# dummyload1.net
KiCad netlist of a schematic drawn in EAGLE
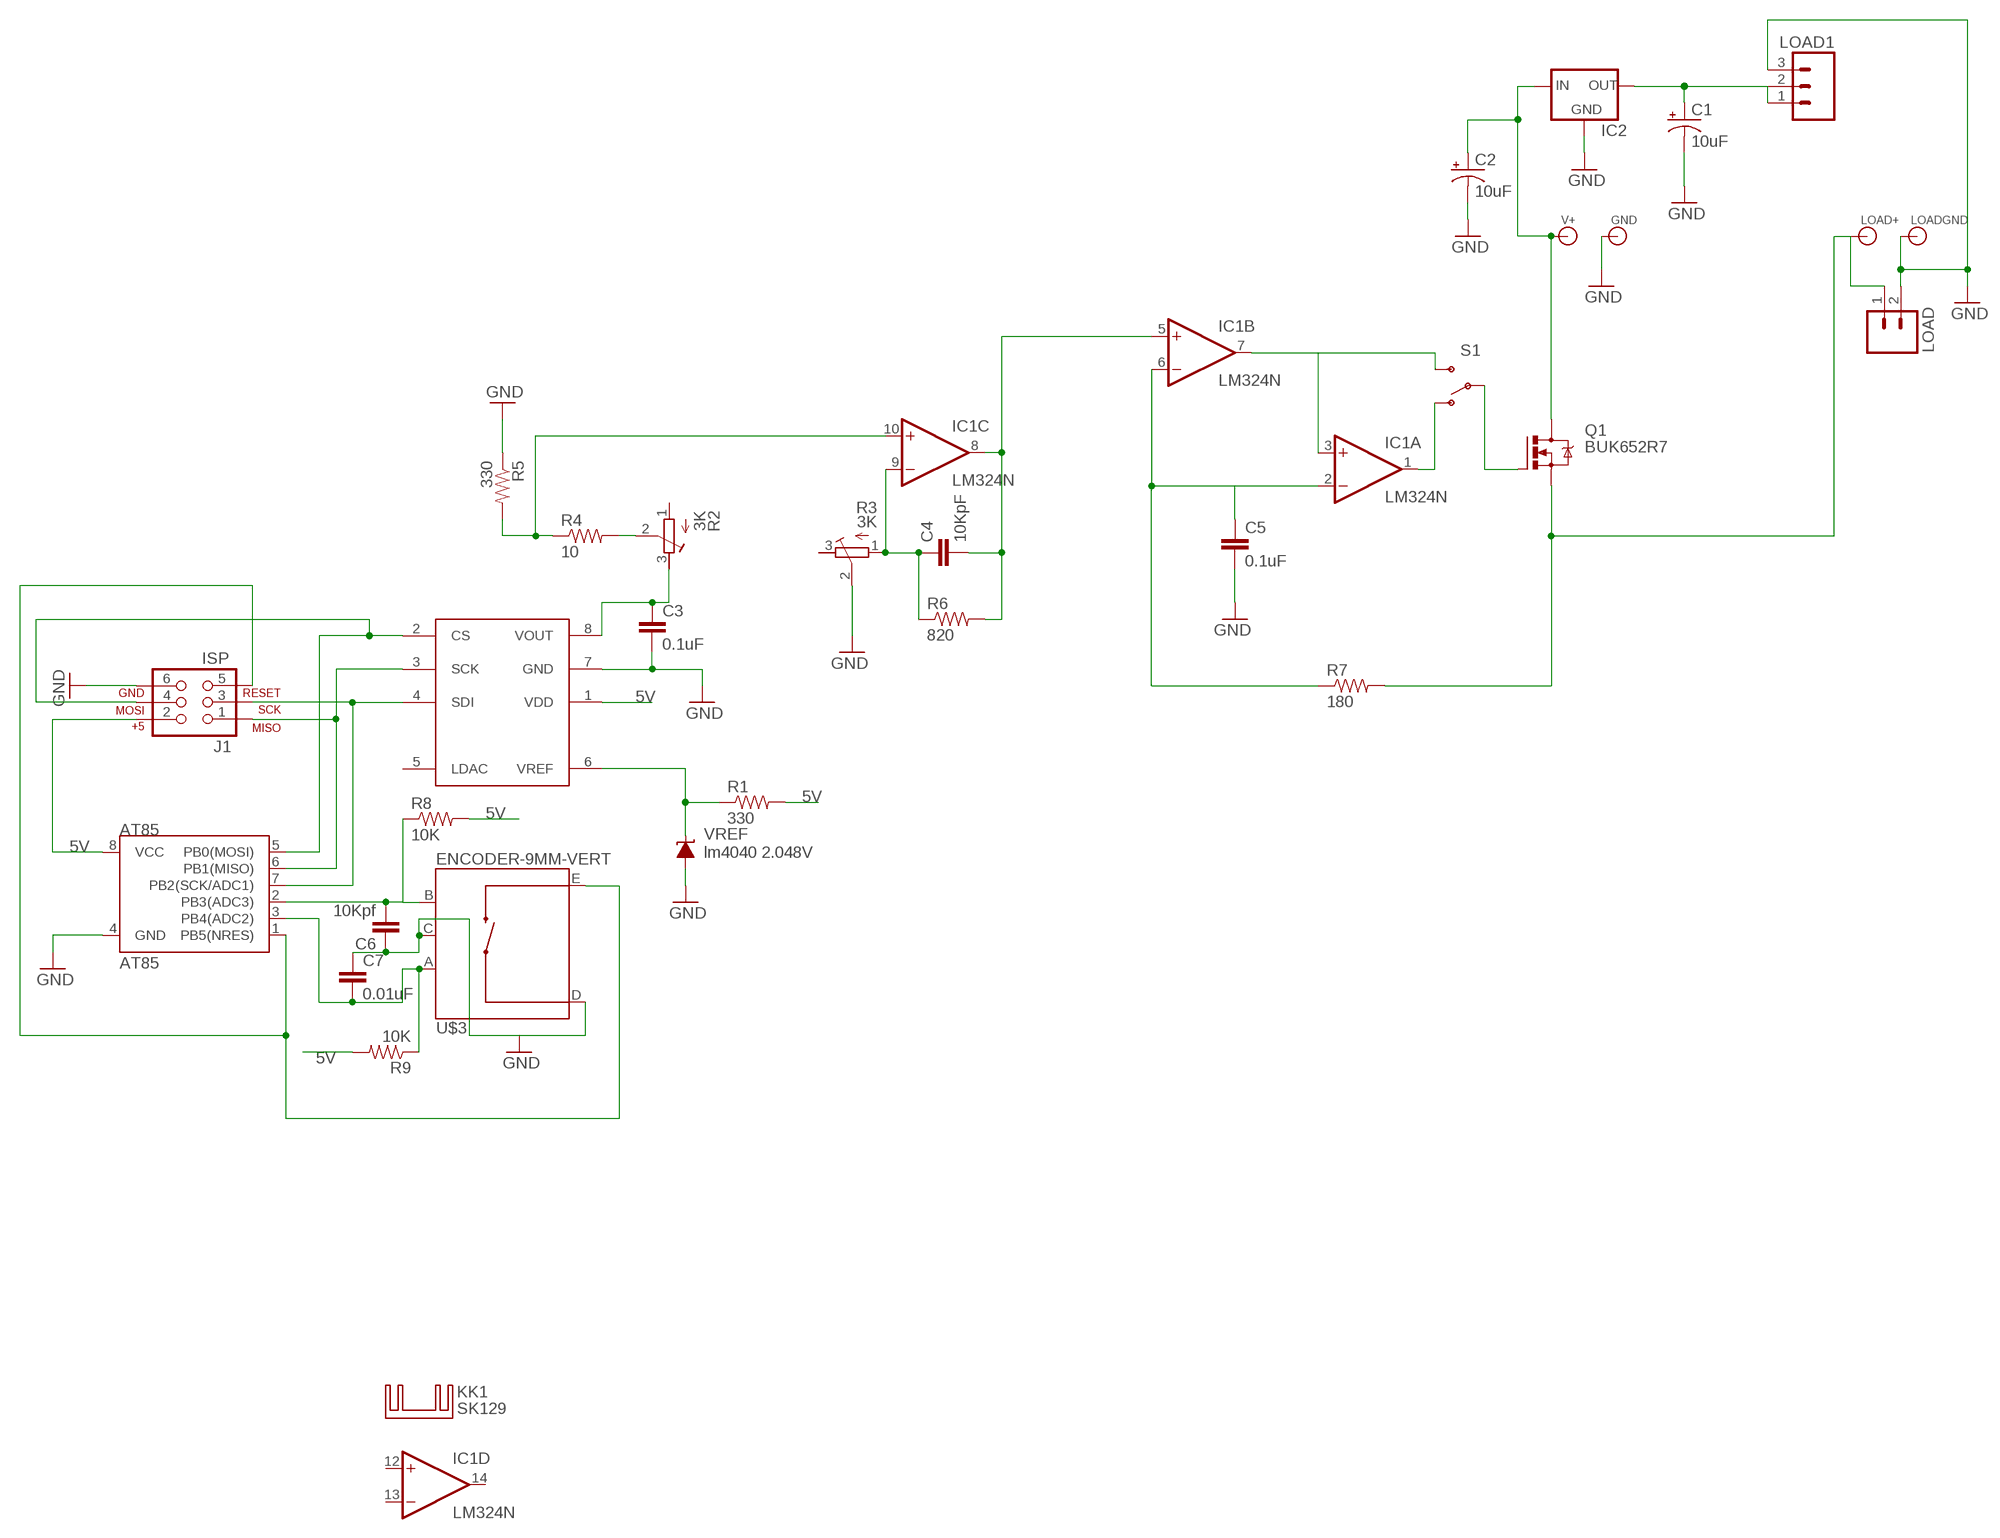
[diagram p0: schematic, sheet 1]

(export (version "E")
  (design (tool "Eeschema 10.0.6"))
  (components
    (comp (ref "AT85")
      (value "AT85")
      (footprint "eagle-import:DIP08")
      (libsource (lib "eagle-import") (part "ATTINY45DIP8"))
    )
    (comp (ref "C1")
      (value "10uF")
      (footprint "eagle-import:CPOL-RADIAL-10UF-25V")
      (libsource (lib "eagle-import") (part "CAP_POLPTH2"))
    )
    (comp (ref "C2")
      (value "10uF")
      (footprint "eagle-import:CPOL-RADIAL-10UF-25V")
      (libsource (lib "eagle-import") (part "CAP_POLPTH2"))
    )
    (comp (ref "C3")
      (value "0.1uF")
      (footprint "eagle-import:CAP-PTH-SMALL2")
      (libsource (lib "eagle-import") (part "CAPPTH2"))
    )
    (comp (ref "C4")
      (value "10KpF")
      (footprint "eagle-import:CAP-PTH-SMALL2")
      (libsource (lib "eagle-import") (part "CAPPTH2"))
    )
    (comp (ref "C5")
      (value "0.1uF")
      (footprint "eagle-import:CAP-PTH-SMALL2")
      (libsource (lib "eagle-import") (part "CAPPTH2"))
    )
    (comp (ref "C6")
      (value "10Kpf")
      (footprint "eagle-import:CAP-PTH-SMALL2")
      (libsource (lib "eagle-import") (part "CAPPTH2"))
    )
    (comp (ref "C7")
      (value "0.01uF")
      (footprint "eagle-import:CAP-PTH-SMALL2")
      (libsource (lib "eagle-import") (part "CAPPTH2"))
    )
    (comp (ref "GND")
      (value "BANANA_CONN")
      (footprint "eagle-import:BANANA_CONN")
      (libsource (lib "eagle-import") (part "BANANA_CONN"))
    )
    (comp (ref "IC1")
      (value "LM324N")
      (footprint "eagle-import:DIL14")
      (libsource (lib "eagle-import") (part "LM324N"))
    )
    (comp (ref "IC2")
      (value "V_REG_78XXSINK")
      (footprint "eagle-import:TO220-IGO")
      (libsource (lib "eagle-import") (part "V_REG_78XXSINK"))
    )
    (comp (ref "J1")
      (value "ISP")
      (footprint "eagle-import:2X3-NS")
      (libsource (lib "eagle-import") (part "AVR_SPI_PRG_6NS"))
    )
    (comp (ref "KK1")
      (value "SK129")
      (footprint "eagle-import:SK129-HOLE")
      (libsource (lib "eagle-import") (part "SK129"))
    )
    (comp (ref "LOAD")
      (value "M02LOCK")
      (footprint "eagle-import:1X02_LOCK")
      (libsource (lib "eagle-import") (part "M02LOCK"))
    )
    (comp (ref "LOAD+")
      (value "BANANA_CONN")
      (footprint "eagle-import:BANANA_CONN")
      (libsource (lib "eagle-import") (part "BANANA_CONN"))
    )
    (comp (ref "LOAD1")
      (value "M031X03_NO_SILK")
      (footprint "eagle-import:1X03_NO_SILK")
      (libsource (lib "eagle-import") (part "M031X03_NO_SILK"))
    )
    (comp (ref "LOADGND")
      (value "BANANA_CONN")
      (footprint "eagle-import:BANANA_CONN")
      (libsource (lib "eagle-import") (part "BANANA_CONN"))
    )
    (comp (ref "Q1")
      (value "BUK652R7")
      (footprint "eagle-import:TO220BV")
      (libsource (lib "eagle-import") (part "IRF540"))
    )
    (comp (ref "R1")
      (value "330")
      (footprint "eagle-import:AXIAL-0.4")
      (libsource (lib "eagle-import") (part "RESISTORPTH-1/4W"))
    )
    (comp (ref "R2")
      (value "3K")
      (footprint "eagle-import:RTRIM3296W")
      (libsource (lib "eagle-import") (part "R-TRIMM3296W"))
    )
    (comp (ref "R3")
      (value "3K")
      (footprint "eagle-import:RTRIM3296W")
      (libsource (lib "eagle-import") (part "R-TRIMM3296W"))
    )
    (comp (ref "R4")
      (value "10")
      (footprint "eagle-import:AXIAL-0.4")
      (libsource (lib "eagle-import") (part "RESISTORPTH-1/4W"))
    )
    (comp (ref "R5")
      (value "330")
      (footprint "eagle-import:AXIAL-0.4")
      (libsource (lib "eagle-import") (part "RESISTORPTH-1/4W"))
    )
    (comp (ref "R6")
      (value "820")
      (footprint "eagle-import:AXIAL-0.4")
      (libsource (lib "eagle-import") (part "RESISTORPTH-1/4W"))
    )
    (comp (ref "R7")
      (value "180")
      (footprint "eagle-import:AXIAL-0.4")
      (libsource (lib "eagle-import") (part "RESISTORPTH-1/4W"))
    )
    (comp (ref "R8")
      (value "10K")
      (footprint "eagle-import:AXIAL-0.4")
      (libsource (lib "eagle-import") (part "RESISTORPTH-1/4W"))
    )
    (comp (ref "R9")
      (value "10K")
      (footprint "eagle-import:AXIAL-0.4")
      (libsource (lib "eagle-import") (part "RESISTORPTH-1/4W"))
    )
    (comp (ref "S1")
      (value "SWITCH-SPSTPTH")
      (footprint "eagle-import:SWITCH-SPDT")
      (libsource (lib "eagle-import") (part "SWITCH-SPSTPTH"))
    )
    (comp (ref "U$2")
      (value "MCP4921")
      (footprint "eagle-import:DIL08")
      (libsource (lib "eagle-import") (part "MCP4921"))
    )
    (comp (ref "U$3")
      (value "ENCODER-9MM-VERT")
      (footprint "eagle-import:ENCODER-5PIN")
      (libsource (lib "eagle-import") (part "ENCODER-9MM-VERT"))
    )
    (comp (ref "V+")
      (value "BANANA_CONN")
      (footprint "eagle-import:BANANA_CONN")
      (libsource (lib "eagle-import") (part "BANANA_CONN"))
    )
    (comp (ref "VREF")
      (value "lm4040 2.048V")
      (footprint "eagle-import:LP_O-PBCY-W3")
      (fields (field (name "MPN") "LM4041C12ILP"))
      (libsource (lib "eagle-import") (part "LM4041LPC12"))
    )
  )
  (nets
    (net (code "1") (name "/5V") (class "Default")
      (node (ref "AT85") (pin "8") (pinfunction "VCC_8") (pintype "bidirectional"))
      (node (ref "C1") (pin "1") (pinfunction "+_1") (pintype "passive"))
      (node (ref "IC2") (pin "OUT") (pinfunction "OUT_OUT") (pintype "output"))
      (node (ref "J1") (pin "2") (pinfunction "2_2") (pintype "passive"))
      (node (ref "LOAD1") (pin "1") (pinfunction "1_1") (pintype "passive"))
      (node (ref "LOAD1") (pin "2") (pinfunction "2_2") (pintype "passive"))
      (node (ref "R1") (pin "P$2") (pinfunction "2_P$2") (pintype "passive"))
      (node (ref "R8") (pin "P$2") (pinfunction "2_P$2") (pintype "passive"))
      (node (ref "R9") (pin "P$2") (pinfunction "2_P$2") (pintype "passive"))
      (node (ref "U$2") (pin "1") (pinfunction "VDD_1") (pintype "bidirectional"))
    )
    (net (code "2") (name "GND") (class "Default")
      (node (ref "AT85") (pin "4") (pinfunction "GND_4") (pintype "bidirectional"))
      (node (ref "C1") (pin "2") (pinfunction "-_2") (pintype "passive"))
      (node (ref "C2") (pin "2") (pinfunction "-_2") (pintype "passive"))
      (node (ref "C3") (pin "2") (pinfunction "2_2") (pintype "passive"))
      (node (ref "C5") (pin "2") (pinfunction "2_2") (pintype "passive"))
      (node (ref "C6") (pin "1") (pinfunction "1_1") (pintype "passive"))
      (node (ref "C7") (pin "1") (pinfunction "1_1") (pintype "passive"))
      (node (ref "GND") (pin "P$1") (pinfunction "1_P$1") (pintype "passive"))
      (node (ref "IC2") (pin "GND") (pinfunction "GND_GND") (pintype "input"))
      (node (ref "J1") (pin "6") (pinfunction "6_6") (pintype "passive"))
      (node (ref "LOAD") (pin "2") (pinfunction "2_2") (pintype "passive"))
      (node (ref "LOAD1") (pin "3") (pinfunction "3_3") (pintype "passive"))
      (node (ref "LOADGND") (pin "P$1") (pinfunction "1_P$1") (pintype "passive"))
      (node (ref "R3") (pin "2") (pinfunction "S_2") (pintype "passive"))
      (node (ref "R5") (pin "P$1") (pinfunction "1_P$1") (pintype "passive"))
      (node (ref "U$2") (pin "7") (pinfunction "GND_7") (pintype "bidirectional"))
      (node (ref "U$3") (pin "C") (pinfunction "C_C") (pintype "bidirectional"))
      (node (ref "U$3") (pin "D") (pinfunction "D_D") (pintype "passive"))
      (node (ref "VREF") (pin "3") (pinfunction "A_3") (pintype "passive"))
    )
    (net (code "3") (name "Net-(AT85-PB0(MOSI))") (class "Default")
      (node (ref "AT85") (pin "5") (pinfunction "PB0(MOSI)_5") (pintype "bidirectional"))
      (node (ref "J1") (pin "4") (pinfunction "4_4") (pintype "passive"))
      (node (ref "U$2") (pin "2") (pinfunction "CS_2") (pintype "bidirectional"))
    )
    (net (code "4") (name "Net-(AT85-PB1(MISO))") (class "Default")
      (node (ref "AT85") (pin "6") (pinfunction "PB1(MISO)_6") (pintype "bidirectional"))
      (node (ref "J1") (pin "1") (pinfunction "1_1") (pintype "passive"))
      (node (ref "U$2") (pin "3") (pinfunction "SCK_3") (pintype "bidirectional"))
    )
    (net (code "5") (name "Net-(AT85-PB2(SCK{slash}ADC1))") (class "Default")
      (node (ref "AT85") (pin "7") (pinfunction "PB2(SCK/ADC1)_7") (pintype "bidirectional"))
      (node (ref "J1") (pin "3") (pinfunction "3_3") (pintype "passive"))
      (node (ref "U$2") (pin "4") (pinfunction "SDI_4") (pintype "bidirectional"))
    )
    (net (code "6") (name "Net-(AT85-PB3(ADC3))") (class "Default")
      (node (ref "AT85") (pin "2") (pinfunction "PB3(ADC3)_2") (pintype "bidirectional"))
      (node (ref "C6") (pin "2") (pinfunction "2_2") (pintype "passive"))
      (node (ref "R8") (pin "P$1") (pinfunction "1_P$1") (pintype "passive"))
      (node (ref "U$3") (pin "B") (pinfunction "B_B") (pintype "bidirectional"))
    )
    (net (code "7") (name "Net-(AT85-PB4(ADC2))") (class "Default")
      (node (ref "AT85") (pin "3") (pinfunction "PB4(ADC2)_3") (pintype "bidirectional"))
      (node (ref "C7") (pin "2") (pinfunction "2_2") (pintype "passive"))
      (node (ref "R9") (pin "P$1") (pinfunction "1_P$1") (pintype "passive"))
      (node (ref "U$3") (pin "A") (pinfunction "A_A") (pintype "bidirectional"))
    )
    (net (code "8") (name "Net-(AT85-PB5(NRES))") (class "Default")
      (node (ref "AT85") (pin "1") (pinfunction "PB5(NRES)_1") (pintype "bidirectional"))
      (node (ref "J1") (pin "5") (pinfunction "5_5") (pintype "passive"))
      (node (ref "U$3") (pin "E") (pinfunction "E_E") (pintype "passive"))
    )
    (net (code "9") (name "Net-(C2-+)") (class "Default")
      (node (ref "C2") (pin "1") (pinfunction "+_1") (pintype "passive"))
      (node (ref "IC2") (pin "IN") (pinfunction "IN_IN") (pintype "input"))
      (node (ref "Q1") (pin "D") (pinfunction "D_D") (pintype "passive"))
      (node (ref "V+") (pin "P$1") (pinfunction "1_P$1") (pintype "passive"))
    )
    (net (code "10") (name "Net-(IC1A-+IN)") (class "Default")
      (node (ref "IC1") (pin "3") (pinfunction "+IN_3") (pintype "input"))
      (node (ref "IC1") (pin "7") (pinfunction "OUT_7") (pintype "output"))
      (node (ref "S1") (pin "3") (pinfunction "S_3") (pintype "passive"))
    )
    (net (code "11") (name "Net-(IC1A--IN)") (class "Default")
      (node (ref "C5") (pin "1") (pinfunction "1_1") (pintype "passive"))
      (node (ref "IC1") (pin "2") (pinfunction "-IN_2") (pintype "input"))
      (node (ref "IC1") (pin "6") (pinfunction "-IN_6") (pintype "input"))
      (node (ref "R7") (pin "P$1") (pinfunction "1_P$1") (pintype "passive"))
    )
    (net (code "12") (name "Net-(IC1A-OUT)") (class "Default")
      (node (ref "IC1") (pin "1") (pinfunction "OUT_1") (pintype "output"))
      (node (ref "S1") (pin "1") (pinfunction "O_1") (pintype "passive"))
    )
    (net (code "13") (name "Net-(IC1B-+IN)") (class "Default")
      (node (ref "C4") (pin "2") (pinfunction "2_2") (pintype "passive"))
      (node (ref "IC1") (pin "5") (pinfunction "+IN_5") (pintype "input"))
      (node (ref "IC1") (pin "8") (pinfunction "OUT_8") (pintype "output"))
      (node (ref "R6") (pin "P$2") (pinfunction "2_P$2") (pintype "passive"))
    )
    (net (code "14") (name "Net-(IC1C-+IN)") (class "Default")
      (node (ref "IC1") (pin "10") (pinfunction "+IN_10") (pintype "input"))
      (node (ref "R4") (pin "P$1") (pinfunction "1_P$1") (pintype "passive"))
      (node (ref "R5") (pin "P$2") (pinfunction "2_P$2") (pintype "passive"))
    )
    (net (code "15") (name "Net-(IC1C--IN)") (class "Default")
      (node (ref "C4") (pin "1") (pinfunction "1_1") (pintype "passive"))
      (node (ref "IC1") (pin "9") (pinfunction "-IN_9") (pintype "input"))
      (node (ref "R3") (pin "1") (pinfunction "A_1") (pintype "passive"))
      (node (ref "R6") (pin "P$1") (pinfunction "1_P$1") (pintype "passive"))
    )
    (net (code "16") (name "Net-(LOAD+-1)") (class "Default")
      (node (ref "LOAD") (pin "1") (pinfunction "1_1") (pintype "passive"))
      (node (ref "LOAD+") (pin "P$1") (pinfunction "1_P$1") (pintype "passive"))
      (node (ref "Q1") (pin "S") (pinfunction "S_S") (pintype "passive"))
      (node (ref "R7") (pin "P$2") (pinfunction "2_P$2") (pintype "passive"))
    )
    (net (code "17") (name "Net-(R1-1)") (class "Default")
      (node (ref "R1") (pin "P$1") (pinfunction "1_P$1") (pintype "passive"))
      (node (ref "U$2") (pin "6") (pinfunction "VREF_6") (pintype "bidirectional"))
      (node (ref "VREF") (pin "2") (pinfunction "C_2") (pintype "passive"))
    )
    (net (code "18") (name "Net-(R2-E)") (class "Default")
      (node (ref "C3") (pin "1") (pinfunction "1_1") (pintype "passive"))
      (node (ref "R2") (pin "3") (pinfunction "E_3") (pintype "passive"))
      (node (ref "U$2") (pin "8") (pinfunction "VOUT_8") (pintype "bidirectional"))
    )
    (net (code "19") (name "Net-(R2-S)") (class "Default")
      (node (ref "R2") (pin "2") (pinfunction "S_2") (pintype "passive"))
      (node (ref "R4") (pin "P$2") (pinfunction "2_P$2") (pintype "passive"))
    )
    (net (code "20") (name "Net-(S1-P)") (class "Default")
      (node (ref "Q1") (pin "G") (pinfunction "G_G") (pintype "passive"))
      (node (ref "S1") (pin "2") (pinfunction "P_2") (pintype "passive"))
    )
    (net (code "21") (name "unconnected-(IC1D-+IN-Pad12)") (class "Default")
      (node (ref "IC1") (pin "12") (pinfunction "+IN_12") (pintype "input"))
    )
    (net (code "22") (name "unconnected-(IC1D--IN-Pad13)") (class "Default")
      (node (ref "IC1") (pin "13") (pinfunction "-IN_13") (pintype "input"))
    )
    (net (code "23") (name "unconnected-(IC1D-OUT-Pad14)") (class "Default")
      (node (ref "IC1") (pin "14") (pinfunction "OUT_14") (pintype "output"))
    )
    (net (code "24") (name "unconnected-(R2-A-Pad1)") (class "Default")
      (node (ref "R2") (pin "1") (pinfunction "A_1") (pintype "passive"))
    )
    (net (code "25") (name "unconnected-(R3-E-Pad3)") (class "Default")
      (node (ref "R3") (pin "3") (pinfunction "E_3") (pintype "passive"))
    )
    (net (code "26") (name "unconnected-(U$2-LDAC-Pad5)") (class "Default")
      (node (ref "U$2") (pin "5") (pinfunction "LDAC_5") (pintype "bidirectional"))
    )
  )
)
